# Bachelorarbeit.net
KiCad netlist of a schematic drawn in EAGLE
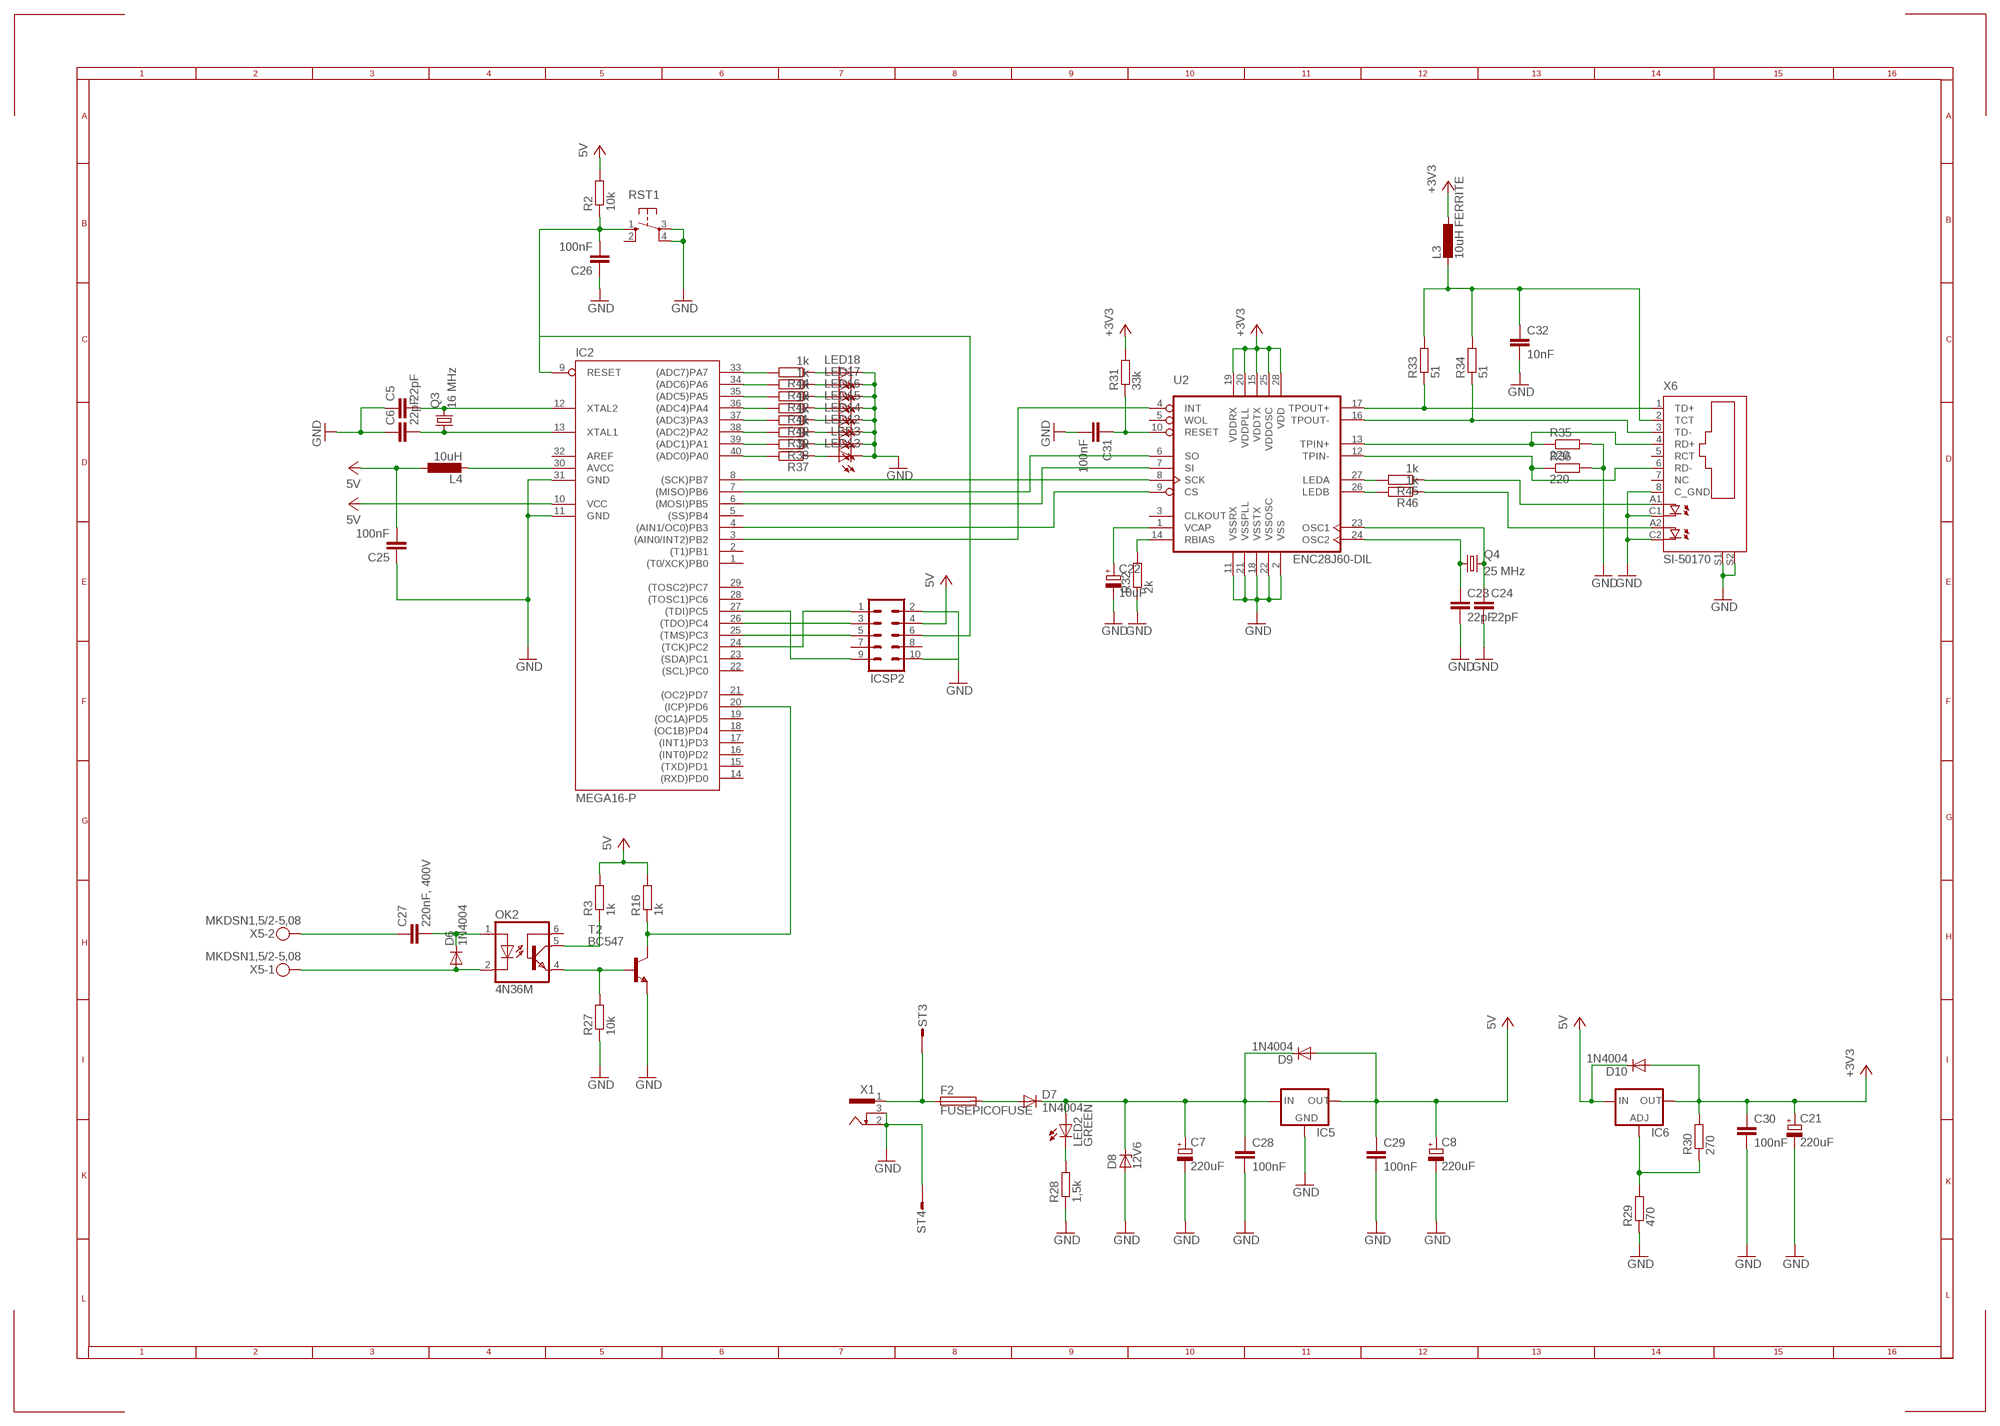
[diagram p0: schematic, sheet 1]

(export (version "E")
  (design (tool "Eeschema 10.0.6"))
  (components
    (comp (ref "C5")
      (value "22pF")
      (footprint "eagle-import:C025-024X044")
      (libsource (lib "eagle-import") (part "C-EU025-024X044"))
    )
    (comp (ref "C6")
      (value "22pF")
      (footprint "eagle-import:C025-024X044")
      (libsource (lib "eagle-import") (part "C-EU025-024X044"))
    )
    (comp (ref "C7")
      (value "220uF")
      (footprint "eagle-import:E3,5-8")
      (libsource (lib "eagle-import") (part "CPOL-EUE3.5-8"))
    )
    (comp (ref "C8")
      (value "220uF")
      (footprint "eagle-import:E3,5-8")
      (libsource (lib "eagle-import") (part "CPOL-EUE3.5-8"))
    )
    (comp (ref "C21")
      (value "220uF")
      (footprint "eagle-import:E3,5-8")
      (libsource (lib "eagle-import") (part "CPOL-EUE3.5-8"))
    )
    (comp (ref "C22")
      (value "10uF")
      (footprint "eagle-import:E3,5-8")
      (libsource (lib "eagle-import") (part "CPOL-EUE3.5-8"))
    )
    (comp (ref "C23")
      (value "22pF")
      (footprint "eagle-import:C025-024X044")
      (libsource (lib "eagle-import") (part "C-EU025-024X044"))
    )
    (comp (ref "C24")
      (value "22pF")
      (footprint "eagle-import:C025-024X044")
      (libsource (lib "eagle-import") (part "C-EU025-024X044"))
    )
    (comp (ref "C25")
      (value "100nF")
      (footprint "eagle-import:C025-025X050")
      (libsource (lib "eagle-import") (part "C-EU025-025X050"))
    )
    (comp (ref "C26")
      (value "100nF")
      (footprint "eagle-import:C025-025X050")
      (libsource (lib "eagle-import") (part "C-EU025-025X050"))
    )
    (comp (ref "C27")
      (value "220nF, 400V")
      (footprint "eagle-import:C025-025X050")
      (libsource (lib "eagle-import") (part "C-EU025-025X050"))
    )
    (comp (ref "C28")
      (value "100nF")
      (footprint "eagle-import:C025-025X050")
      (libsource (lib "eagle-import") (part "C-EU025-025X050"))
    )
    (comp (ref "C29")
      (value "100nF")
      (footprint "eagle-import:C025-025X050")
      (libsource (lib "eagle-import") (part "C-EU025-025X050"))
    )
    (comp (ref "C30")
      (value "100nF")
      (footprint "eagle-import:C025-025X050")
      (libsource (lib "eagle-import") (part "C-EU025-025X050"))
    )
    (comp (ref "C31")
      (value "100nF")
      (footprint "eagle-import:C025-025X050")
      (libsource (lib "eagle-import") (part "C-EU025-025X050"))
    )
    (comp (ref "C32")
      (value "10nF")
      (footprint "eagle-import:C025-025X050")
      (libsource (lib "eagle-import") (part "C-EU025-025X050"))
    )
    (comp (ref "D6")
      (value "1N4004")
      (footprint "eagle-import:DO41-10")
      (libsource (lib "eagle-import") (part "1N4004"))
    )
    (comp (ref "D7")
      (value "1N4004")
      (footprint "eagle-import:DO41-10")
      (libsource (lib "eagle-import") (part "1N4004"))
    )
    (comp (ref "D8")
      (value "12V6")
      (footprint "eagle-import:DO34Z7")
      (libsource (lib "eagle-import") (part "BZX90"))
    )
    (comp (ref "D9")
      (value "1N4004")
      (footprint "eagle-import:DO41-10")
      (libsource (lib "eagle-import") (part "1N4004"))
    )
    (comp (ref "D10")
      (value "1N4004")
      (footprint "eagle-import:DO41-10")
      (libsource (lib "eagle-import") (part "1N4004"))
    )
    (comp (ref "F2")
      (value "FUSEPICOFUSE")
      (footprint "eagle-import:PICOFUSE")
      (libsource (lib "eagle-import") (part "FUSEPICOFUSE"))
    )
    (comp (ref "IC2")
      (value "MEGA16-P")
      (footprint "eagle-import:DIL40")
      (fields (field (name "MPN") "ATMEGA16-16PU"))
      (libsource (lib "eagle-import") (part "MEGA16-P"))
    )
    (comp (ref "IC5")
      (value "78XXS")
      (footprint "eagle-import:78XXS")
      (libsource (lib "eagle-import") (part "78XXS"))
    )
    (comp (ref "IC6")
      (value "LM317TS")
      (footprint "eagle-import:317TS")
      (libsource (lib "eagle-import") (part "LM317TS"))
    )
    (comp (ref "ICSP2")
      (value "10V")
      (footprint "eagle-import:10V")
      (libsource (lib "eagle-import") (part "10V"))
    )
    (comp (ref "L3")
      (value "10uH FERRITE")
      (footprint "eagle-import:0204_5")
      (libsource (lib "eagle-import") (part "L-EU0204/5"))
    )
    (comp (ref "L4")
      (value "10uH")
      (footprint "eagle-import:0204_5")
      (libsource (lib "eagle-import") (part "L-EU0204/5"))
    )
    (comp (ref "LED2")
      (value "GREEN")
      (footprint "eagle-import:LED3MM")
      (libsource (lib "eagle-import") (part "LED3MM"))
    )
    (comp (ref "LED3")
      (value "LED3MM")
      (footprint "eagle-import:LED3MM")
      (libsource (lib "eagle-import") (part "LED3MM"))
    )
    (comp (ref "LED12")
      (value "LED3MM")
      (footprint "eagle-import:LED3MM")
      (libsource (lib "eagle-import") (part "LED3MM"))
    )
    (comp (ref "LED13")
      (value "LED3MM")
      (footprint "eagle-import:LED3MM")
      (libsource (lib "eagle-import") (part "LED3MM"))
    )
    (comp (ref "LED14")
      (value "LED3MM")
      (footprint "eagle-import:LED3MM")
      (libsource (lib "eagle-import") (part "LED3MM"))
    )
    (comp (ref "LED15")
      (value "LED3MM")
      (footprint "eagle-import:LED3MM")
      (libsource (lib "eagle-import") (part "LED3MM"))
    )
    (comp (ref "LED16")
      (value "LED3MM")
      (footprint "eagle-import:LED3MM")
      (libsource (lib "eagle-import") (part "LED3MM"))
    )
    (comp (ref "LED17")
      (value "LED3MM")
      (footprint "eagle-import:LED3MM")
      (libsource (lib "eagle-import") (part "LED3MM"))
    )
    (comp (ref "LED18")
      (value "LED3MM")
      (footprint "eagle-import:LED3MM")
      (libsource (lib "eagle-import") (part "LED3MM"))
    )
    (comp (ref "OK2")
      (value "4N36M")
      (footprint "eagle-import:DIL06")
      (fields (field (name "MPN") "4N36-M"))
      (libsource (lib "eagle-import") (part "4N?M36"))
    )
    (comp (ref "Q3")
      (value "16 MHz")
      (footprint "eagle-import:HC49U-V")
      (libsource (lib "eagle-import") (part "CRYSTALHC49U-V"))
    )
    (comp (ref "Q4")
      (value "25 MHz")
      (footprint "eagle-import:HC49U-V")
      (libsource (lib "eagle-import") (part "CRYSTALHC49U-V"))
    )
    (comp (ref "R2")
      (value "10k")
      (footprint "eagle-import:0207_10")
      (libsource (lib "eagle-import") (part "R-EU_0207/10"))
    )
    (comp (ref "R3")
      (value "1k")
      (footprint "eagle-import:0207_10")
      (libsource (lib "eagle-import") (part "R-EU_0207/10"))
    )
    (comp (ref "R16")
      (value "1k")
      (footprint "eagle-import:0207_10")
      (libsource (lib "eagle-import") (part "R-EU_0207/10"))
    )
    (comp (ref "R27")
      (value "10k")
      (footprint "eagle-import:0207_10")
      (libsource (lib "eagle-import") (part "R-EU_0207/10"))
    )
    (comp (ref "R28")
      (value "1,5k")
      (footprint "eagle-import:0207_10")
      (libsource (lib "eagle-import") (part "R-EU_0207/10"))
    )
    (comp (ref "R29")
      (value "470")
      (footprint "eagle-import:0207_10")
      (libsource (lib "eagle-import") (part "R-EU_0207/10"))
    )
    (comp (ref "R30")
      (value "270")
      (footprint "eagle-import:0207_10")
      (libsource (lib "eagle-import") (part "R-EU_0207/10"))
    )
    (comp (ref "R31")
      (value "33k")
      (footprint "eagle-import:0207_10")
      (libsource (lib "eagle-import") (part "R-EU_0207/10"))
    )
    (comp (ref "R32")
      (value "2k")
      (footprint "eagle-import:0207_10")
      (libsource (lib "eagle-import") (part "R-EU_0207/10"))
    )
    (comp (ref "R33")
      (value "51")
      (footprint "eagle-import:0207_10")
      (libsource (lib "eagle-import") (part "R-EU_0207/10"))
    )
    (comp (ref "R34")
      (value "51")
      (footprint "eagle-import:0207_10")
      (libsource (lib "eagle-import") (part "R-EU_0207/10"))
    )
    (comp (ref "R35")
      (value "220")
      (footprint "eagle-import:0207_10")
      (libsource (lib "eagle-import") (part "R-EU_0207/10"))
    )
    (comp (ref "R36")
      (value "220")
      (footprint "eagle-import:0207_10")
      (libsource (lib "eagle-import") (part "R-EU_0207/10"))
    )
    (comp (ref "R37")
      (value "1k")
      (footprint "eagle-import:0207_10")
      (libsource (lib "eagle-import") (part "R-EU_0207/10"))
    )
    (comp (ref "R38")
      (value "1k")
      (footprint "eagle-import:0207_10")
      (libsource (lib "eagle-import") (part "R-EU_0207/10"))
    )
    (comp (ref "R39")
      (value "1k")
      (footprint "eagle-import:0207_10")
      (libsource (lib "eagle-import") (part "R-EU_0207/10"))
    )
    (comp (ref "R40")
      (value "1k")
      (footprint "eagle-import:0207_10")
      (libsource (lib "eagle-import") (part "R-EU_0207/10"))
    )
    (comp (ref "R41")
      (value "1k")
      (footprint "eagle-import:0207_10")
      (libsource (lib "eagle-import") (part "R-EU_0207/10"))
    )
    (comp (ref "R42")
      (value "1k")
      (footprint "eagle-import:0207_10")
      (libsource (lib "eagle-import") (part "R-EU_0207/10"))
    )
    (comp (ref "R43")
      (value "1k")
      (footprint "eagle-import:0207_10")
      (libsource (lib "eagle-import") (part "R-EU_0207/10"))
    )
    (comp (ref "R44")
      (value "1k")
      (footprint "eagle-import:0207_10")
      (libsource (lib "eagle-import") (part "R-EU_0207/10"))
    )
    (comp (ref "R45")
      (value "1k")
      (footprint "eagle-import:0207_10")
      (libsource (lib "eagle-import") (part "R-EU_0207/10"))
    )
    (comp (ref "R46")
      (value "1k")
      (footprint "eagle-import:0207_10")
      (libsource (lib "eagle-import") (part "R-EU_0207/10"))
    )
    (comp (ref "RST1")
      (value "10-XX")
      (footprint "eagle-import:B3F-10XX")
      (fields (field (name "MPN") "B3F-1000"))
      (libsource (lib "eagle-import") (part "10-XX"))
    )
    (comp (ref "ST3")
      (value "ST2,8")
      (footprint "eagle-import:ST2,8")
      (libsource (lib "eagle-import") (part "ST2,8"))
    )
    (comp (ref "ST4")
      (value "ST2,8")
      (footprint "eagle-import:ST2,8")
      (libsource (lib "eagle-import") (part "ST2,8"))
    )
    (comp (ref "T2")
      (value "BC547")
      (footprint "eagle-import:TO92")
      (libsource (lib "eagle-import") (part "BC547"))
    )
    (comp (ref "U2")
      (value "ENC28J60-DIL")
      (footprint "eagle-import:DIL28-3")
      (libsource (lib "eagle-import") (part "ENC28J60-DIL"))
    )
    (comp (ref "X1")
      (value "SCD-014A")
      (footprint "eagle-import:SCD-014-A")
      (libsource (lib "eagle-import") (part "SCD-014A"))
    )
    (comp (ref "X5")
      (value "MKDSN1,5/2-5,08")
      (footprint "eagle-import:MKDSN1,5_2-5,08")
      (fields (field (name "MPN") "MKDSN 1,5/2-5.08"))
      (libsource (lib "eagle-import") (part "MKDSN1,5/2-5,08"))
    )
    (comp (ref "X6")
      (value "SI-50170")
      (footprint "eagle-import:SI-50170")
      (libsource (lib "eagle-import") (part "SI-50170"))
    )
  )
  (nets
    (net (code "1") (name "+3V3") (class "Default")
      (node (ref "C21") (pin "+") (pinfunction "+_+") (pintype "passive"))
      (node (ref "C25") (pin "2") (pinfunction "2_2") (pintype "passive"))
      (node (ref "C29") (pin "1") (pinfunction "1_1") (pintype "passive"))
      (node (ref "C30") (pin "1") (pinfunction "1_1") (pintype "passive"))
      (node (ref "C8") (pin "+") (pinfunction "+_+") (pintype "passive"))
      (node (ref "D10") (pin "A") (pinfunction "A_A") (pintype "passive"))
      (node (ref "D10") (pin "C") (pinfunction "C_C") (pintype "passive"))
      (node (ref "D9") (pin "A") (pinfunction "A_A") (pintype "passive"))
      (node (ref "IC2") (pin "10") (pinfunction "VCC_10") (pintype "power_in"))
      (node (ref "IC5") (pin "OUT") (pinfunction "OUT_OUT") (pintype "passive"))
      (node (ref "IC6") (pin "2") (pinfunction "OUT_2") (pintype "passive"))
      (node (ref "IC6") (pin "3") (pinfunction "IN_3") (pintype "input"))
      (node (ref "ICSP2") (pin "4") (pinfunction "4_4") (pintype "passive"))
      (node (ref "L3") (pin "1") (pinfunction "1_1") (pintype "passive"))
      (node (ref "L4") (pin "1") (pinfunction "1_1") (pintype "passive"))
      (node (ref "R16") (pin "2") (pinfunction "2_2") (pintype "passive"))
      (node (ref "R2") (pin "2") (pinfunction "2_2") (pintype "passive"))
      (node (ref "R3") (pin "2") (pinfunction "2_2") (pintype "passive"))
      (node (ref "R30") (pin "2") (pinfunction "2_2") (pintype "passive"))
      (node (ref "R31") (pin "2") (pinfunction "2_2") (pintype "passive"))
      (node (ref "U2") (pin "15") (pinfunction "VDDTX_15") (pintype "power_in"))
      (node (ref "U2") (pin "19") (pinfunction "VDDRX_19") (pintype "power_in"))
      (node (ref "U2") (pin "20") (pinfunction "VDDPLL_20") (pintype "power_in"))
      (node (ref "U2") (pin "25") (pinfunction "VDDOSC_25") (pintype "power_in"))
      (node (ref "U2") (pin "28") (pinfunction "VDD_28") (pintype "power_in"))
    )
    (net (code "2") (name "GND") (class "Default")
      (node (ref "C21") (pin "-") (pinfunction "-_-") (pintype "passive"))
      (node (ref "C22") (pin "-") (pinfunction "-_-") (pintype "passive"))
      (node (ref "C23") (pin "2") (pinfunction "2_2") (pintype "passive"))
      (node (ref "C24") (pin "2") (pinfunction "2_2") (pintype "passive"))
      (node (ref "C25") (pin "1") (pinfunction "1_1") (pintype "passive"))
      (node (ref "C26") (pin "1") (pinfunction "1_1") (pintype "passive"))
      (node (ref "C28") (pin "2") (pinfunction "2_2") (pintype "passive"))
      (node (ref "C29") (pin "2") (pinfunction "2_2") (pintype "passive"))
      (node (ref "C30") (pin "2") (pinfunction "2_2") (pintype "passive"))
      (node (ref "C31") (pin "2") (pinfunction "2_2") (pintype "passive"))
      (node (ref "C32") (pin "2") (pinfunction "2_2") (pintype "passive"))
      (node (ref "C5") (pin "1") (pinfunction "1_1") (pintype "passive"))
      (node (ref "C6") (pin "1") (pinfunction "1_1") (pintype "passive"))
      (node (ref "C7") (pin "-") (pinfunction "-_-") (pintype "passive"))
      (node (ref "C8") (pin "-") (pinfunction "-_-") (pintype "passive"))
      (node (ref "D8") (pin "A") (pinfunction "A_A") (pintype "passive"))
      (node (ref "IC2") (pin "11") (pinfunction "GND_11") (pintype "power_in"))
      (node (ref "IC2") (pin "31") (pinfunction "GND_31") (pintype "power_in"))
      (node (ref "IC5") (pin "GND") (pinfunction "GND_GND") (pintype "input"))
      (node (ref "ICSP2") (pin "10") (pinfunction "10_10") (pintype "passive"))
      (node (ref "ICSP2") (pin "2") (pinfunction "2_2") (pintype "passive"))
      (node (ref "LED12") (pin "K") (pinfunction "C_K") (pintype "passive"))
      (node (ref "LED13") (pin "K") (pinfunction "C_K") (pintype "passive"))
      (node (ref "LED14") (pin "K") (pinfunction "C_K") (pintype "passive"))
      (node (ref "LED15") (pin "K") (pinfunction "C_K") (pintype "passive"))
      (node (ref "LED16") (pin "K") (pinfunction "C_K") (pintype "passive"))
      (node (ref "LED17") (pin "K") (pinfunction "C_K") (pintype "passive"))
      (node (ref "LED18") (pin "K") (pinfunction "C_K") (pintype "passive"))
      (node (ref "LED3") (pin "K") (pinfunction "C_K") (pintype "passive"))
      (node (ref "R27") (pin "1") (pinfunction "1_1") (pintype "passive"))
      (node (ref "R28") (pin "1") (pinfunction "1_1") (pintype "passive"))
      (node (ref "R29") (pin "1") (pinfunction "1_1") (pintype "passive"))
      (node (ref "R32") (pin "1") (pinfunction "1_1") (pintype "passive"))
      (node (ref "R35") (pin "2") (pinfunction "2_2") (pintype "passive"))
      (node (ref "R36") (pin "2") (pinfunction "2_2") (pintype "passive"))
      (node (ref "RST1") (pin "3") (pinfunction "P_3") (pintype "passive"))
      (node (ref "RST1") (pin "4") (pinfunction "P1_4") (pintype "passive"))
      (node (ref "ST4") (pin "1") (pinfunction "ST_1") (pintype "passive"))
      (node (ref "T2") (pin "1") (pinfunction "E_1") (pintype "passive"))
      (node (ref "U2") (pin "11") (pinfunction "VSSRX_11") (pintype "power_in"))
      (node (ref "U2") (pin "18") (pinfunction "VSSTX_18") (pintype "power_in"))
      (node (ref "U2") (pin "2") (pinfunction "VSS_2") (pintype "power_in"))
      (node (ref "U2") (pin "21") (pinfunction "VSSPLL_21") (pintype "power_in"))
      (node (ref "U2") (pin "22") (pinfunction "VSSOSC_22") (pintype "power_in"))
      (node (ref "X1") (pin "2") (pinfunction "2_2") (pintype "passive"))
      (node (ref "X1") (pin "3") (pinfunction "3_3") (pintype "passive"))
      (node (ref "X6") (pin "8") (pinfunction "C_GND_8") (pintype "passive"))
      (node (ref "X6") (pin "C1") (pinfunction "C_C1") (pintype "passive"))
      (node (ref "X6") (pin "C2") (pinfunction "C1_C2") (pintype "passive"))
      (node (ref "X6") (pin "S1") (pinfunction "S1_S1") (pintype "passive"))
      (node (ref "X6") (pin "S2") (pinfunction "S2_S2") (pintype "passive"))
    )
    (net (code "3") (name "Net-(C28-Pad1)") (class "Default")
      (node (ref "C28") (pin "1") (pinfunction "1_1") (pintype "passive"))
      (node (ref "C7") (pin "+") (pinfunction "+_+") (pintype "passive"))
      (node (ref "D7") (pin "C") (pinfunction "C_C") (pintype "passive"))
      (node (ref "D8") (pin "C") (pinfunction "C_C") (pintype "passive"))
      (node (ref "D9") (pin "C") (pinfunction "C_C") (pintype "passive"))
      (node (ref "IC5") (pin "IN") (pinfunction "IN_IN") (pintype "input"))
      (node (ref "LED2") (pin "A") (pinfunction "A_A") (pintype "passive"))
    )
    (net (code "4") (name "Net-(D7-PadA)") (class "Default")
      (node (ref "D7") (pin "A") (pinfunction "A_A") (pintype "passive"))
      (node (ref "F2") (pin "2") (pinfunction "2_2") (pintype "passive"))
    )
    (net (code "5") (name "Net-(IC2-(ADC0)PA0)") (class "Default")
      (node (ref "IC2") (pin "40") (pinfunction "(ADC0)PA0_40") (pintype "bidirectional"))
      (node (ref "R37") (pin "2") (pinfunction "2_2") (pintype "passive"))
    )
    (net (code "6") (name "Net-(IC2-(ADC1)PA1)") (class "Default")
      (node (ref "IC2") (pin "39") (pinfunction "(ADC1)PA1_39") (pintype "bidirectional"))
      (node (ref "R38") (pin "2") (pinfunction "2_2") (pintype "passive"))
    )
    (net (code "7") (name "Net-(IC2-(ADC2)PA2)") (class "Default")
      (node (ref "IC2") (pin "38") (pinfunction "(ADC2)PA2_38") (pintype "bidirectional"))
      (node (ref "R39") (pin "2") (pinfunction "2_2") (pintype "passive"))
    )
    (net (code "8") (name "Net-(IC2-(ADC3)PA3)") (class "Default")
      (node (ref "IC2") (pin "37") (pinfunction "(ADC3)PA3_37") (pintype "bidirectional"))
      (node (ref "R40") (pin "2") (pinfunction "2_2") (pintype "passive"))
    )
    (net (code "9") (name "Net-(IC2-(ADC4)PA4)") (class "Default")
      (node (ref "IC2") (pin "36") (pinfunction "(ADC4)PA4_36") (pintype "bidirectional"))
      (node (ref "R41") (pin "2") (pinfunction "2_2") (pintype "passive"))
    )
    (net (code "10") (name "Net-(IC2-(ADC5)PA5)") (class "Default")
      (node (ref "IC2") (pin "35") (pinfunction "(ADC5)PA5_35") (pintype "bidirectional"))
      (node (ref "R42") (pin "2") (pinfunction "2_2") (pintype "passive"))
    )
    (net (code "11") (name "Net-(IC2-(ADC6)PA6)") (class "Default")
      (node (ref "IC2") (pin "34") (pinfunction "(ADC6)PA6_34") (pintype "bidirectional"))
      (node (ref "R43") (pin "2") (pinfunction "2_2") (pintype "passive"))
    )
    (net (code "12") (name "Net-(IC2-(ADC7)PA7)") (class "Default")
      (node (ref "IC2") (pin "33") (pinfunction "(ADC7)PA7_33") (pintype "bidirectional"))
      (node (ref "R44") (pin "2") (pinfunction "2_2") (pintype "passive"))
    )
    (net (code "13") (name "Net-(IC2-(AIN0{slash}INT2)PB2)") (class "Default")
      (node (ref "IC2") (pin "3") (pinfunction "(AIN0/INT2)PB2_3") (pintype "bidirectional"))
      (node (ref "U2") (pin "4") (pinfunction "INT_4") (pintype "output"))
    )
    (net (code "14") (name "Net-(IC2-(AIN1{slash}OC0)PB3)") (class "Default")
      (node (ref "IC2") (pin "4") (pinfunction "(AIN1/OC0)PB3_4") (pintype "bidirectional"))
      (node (ref "U2") (pin "9") (pinfunction "CS_9") (pintype "input"))
    )
    (net (code "15") (name "Net-(IC2-(ICP)PD6)") (class "Default")
      (node (ref "IC2") (pin "20") (pinfunction "(ICP)PD6_20") (pintype "bidirectional"))
      (node (ref "R16") (pin "1") (pinfunction "1_1") (pintype "passive"))
      (node (ref "T2") (pin "3") (pinfunction "C_3") (pintype "passive"))
    )
    (net (code "16") (name "Net-(IC2-(MISO)PB6)") (class "Default")
      (node (ref "IC2") (pin "7") (pinfunction "(MISO)PB6_7") (pintype "bidirectional"))
      (node (ref "U2") (pin "6") (pinfunction "SO_6") (pintype "open_collector"))
    )
    (net (code "17") (name "Net-(IC2-(MOSI)PB5)") (class "Default")
      (node (ref "IC2") (pin "6") (pinfunction "(MOSI)PB5_6") (pintype "bidirectional"))
      (node (ref "U2") (pin "7") (pinfunction "SI_7") (pintype "input"))
    )
    (net (code "18") (name "Net-(IC2-(SCK)PB7)") (class "Default")
      (node (ref "IC2") (pin "8") (pinfunction "(SCK)PB7_8") (pintype "bidirectional"))
      (node (ref "U2") (pin "8") (pinfunction "SCK_8") (pintype "input"))
    )
    (net (code "19") (name "Net-(IC2-(TCK)PC2)") (class "Default")
      (node (ref "IC2") (pin "24") (pinfunction "(TCK)PC2_24") (pintype "bidirectional"))
      (node (ref "ICSP2") (pin "1") (pinfunction "1_1") (pintype "passive"))
    )
    (net (code "20") (name "Net-(IC2-(TDI)PC5)") (class "Default")
      (node (ref "IC2") (pin "27") (pinfunction "(TDI)PC5_27") (pintype "bidirectional"))
      (node (ref "ICSP2") (pin "9") (pinfunction "9_9") (pintype "passive"))
    )
    (net (code "21") (name "Net-(IC2-(TDO)PC4)") (class "Default")
      (node (ref "IC2") (pin "26") (pinfunction "(TDO)PC4_26") (pintype "bidirectional"))
      (node (ref "ICSP2") (pin "3") (pinfunction "3_3") (pintype "passive"))
    )
    (net (code "22") (name "Net-(IC2-(TMS)PC3)") (class "Default")
      (node (ref "IC2") (pin "25") (pinfunction "(TMS)PC3_25") (pintype "bidirectional"))
      (node (ref "ICSP2") (pin "5") (pinfunction "5_5") (pintype "passive"))
    )
    (net (code "23") (name "Net-(IC2-AVCC)") (class "Default")
      (node (ref "IC2") (pin "30") (pinfunction "AVCC_30") (pintype "power_in"))
      (node (ref "L4") (pin "2") (pinfunction "2_2") (pintype "passive"))
    )
    (net (code "24") (name "Net-(IC2-RESET)") (class "Default")
      (node (ref "C26") (pin "2") (pinfunction "2_2") (pintype "passive"))
      (node (ref "IC2") (pin "9") (pinfunction "RESET_9") (pintype "input"))
      (node (ref "ICSP2") (pin "6") (pinfunction "6_6") (pintype "passive"))
      (node (ref "R2") (pin "1") (pinfunction "1_1") (pintype "passive"))
      (node (ref "RST1") (pin "1") (pinfunction "S_1") (pintype "passive"))
    )
    (net (code "25") (name "Net-(IC2-XTAL1)") (class "Default")
      (node (ref "C6") (pin "2") (pinfunction "2_2") (pintype "passive"))
      (node (ref "IC2") (pin "13") (pinfunction "XTAL1_13") (pintype "bidirectional"))
      (node (ref "Q3") (pin "1") (pinfunction "1_1") (pintype "passive"))
    )
    (net (code "26") (name "Net-(IC2-XTAL2)") (class "Default")
      (node (ref "C5") (pin "2") (pinfunction "2_2") (pintype "passive"))
      (node (ref "IC2") (pin "12") (pinfunction "XTAL2_12") (pintype "bidirectional"))
      (node (ref "Q3") (pin "2") (pinfunction "2_2") (pintype "passive"))
    )
    (net (code "27") (name "Net-(IC6-ADJ)") (class "Default")
      (node (ref "IC6") (pin "1") (pinfunction "ADJ_1") (pintype "input"))
      (node (ref "R29") (pin "2") (pinfunction "2_2") (pintype "passive"))
      (node (ref "R30") (pin "1") (pinfunction "1_1") (pintype "passive"))
    )
    (net (code "28") (name "Net-(LED2-C)") (class "Default")
      (node (ref "LED2") (pin "K") (pinfunction "C_K") (pintype "passive"))
      (node (ref "R28") (pin "2") (pinfunction "2_2") (pintype "passive"))
    )
    (net (code "29") (name "Net-(LED3-PadA)") (class "Default")
      (node (ref "LED3") (pin "A") (pinfunction "A_A") (pintype "passive"))
      (node (ref "R38") (pin "1") (pinfunction "1_1") (pintype "passive"))
    )
    (net (code "30") (name "Net-(LED12-PadA)") (class "Default")
      (node (ref "LED12") (pin "A") (pinfunction "A_A") (pintype "passive"))
      (node (ref "R39") (pin "1") (pinfunction "1_1") (pintype "passive"))
    )
    (net (code "31") (name "Net-(LED13-PadA)") (class "Default")
      (node (ref "LED13") (pin "A") (pinfunction "A_A") (pintype "passive"))
      (node (ref "R37") (pin "1") (pinfunction "1_1") (pintype "passive"))
    )
    (net (code "32") (name "Net-(LED14-PadA)") (class "Default")
      (node (ref "LED14") (pin "A") (pinfunction "A_A") (pintype "passive"))
      (node (ref "R40") (pin "1") (pinfunction "1_1") (pintype "passive"))
    )
    (net (code "33") (name "Net-(LED15-PadA)") (class "Default")
      (node (ref "LED15") (pin "A") (pinfunction "A_A") (pintype "passive"))
      (node (ref "R41") (pin "1") (pinfunction "1_1") (pintype "passive"))
    )
    (net (code "34") (name "Net-(LED16-PadA)") (class "Default")
      (node (ref "LED16") (pin "A") (pinfunction "A_A") (pintype "passive"))
      (node (ref "R42") (pin "1") (pinfunction "1_1") (pintype "passive"))
    )
    (net (code "35") (name "Net-(LED17-PadA)") (class "Default")
      (node (ref "LED17") (pin "A") (pinfunction "A_A") (pintype "passive"))
      (node (ref "R43") (pin "1") (pinfunction "1_1") (pintype "passive"))
    )
    (net (code "36") (name "Net-(LED18-PadA)") (class "Default")
      (node (ref "LED18") (pin "A") (pinfunction "A_A") (pintype "passive"))
      (node (ref "R44") (pin "1") (pinfunction "1_1") (pintype "passive"))
    )
    (net (code "37") (name "Net-(OK2-A)") (class "Default")
      (node (ref "C27") (pin "2") (pinfunction "2_2") (pintype "passive"))
      (node (ref "D6") (pin "C") (pinfunction "C_C") (pintype "passive"))
      (node (ref "OK2") (pin "1") (pinfunction "A_1") (pintype "passive"))
    )
    (net (code "38") (name "Net-(OK2-C)") (class "Default")
      (node (ref "D6") (pin "A") (pinfunction "A_A") (pintype "passive"))
      (node (ref "OK2") (pin "2") (pinfunction "C_2") (pintype "passive"))
      (node (ref "X5") (pin "1") (pinfunction "KL_1") (pintype "passive"))
    )
    (net (code "39") (name "Net-(OK2-COL)") (class "Default")
      (node (ref "OK2") (pin "5") (pinfunction "COL_5") (pintype "passive"))
      (node (ref "R3") (pin "1") (pinfunction "1_1") (pintype "passive"))
    )
    (net (code "40") (name "Net-(OK2-EMI)") (class "Default")
      (node (ref "OK2") (pin "4") (pinfunction "EMI_4") (pintype "passive"))
      (node (ref "R27") (pin "2") (pinfunction "2_2") (pintype "passive"))
      (node (ref "T2") (pin "2") (pinfunction "B_2") (pintype "passive"))
    )
    (net (code "41") (name "Net-(ST3-ST)") (class "Default")
      (node (ref "F2") (pin "1") (pinfunction "1_1") (pintype "passive"))
      (node (ref "ST3") (pin "1") (pinfunction "ST_1") (pintype "passive"))
      (node (ref "X1") (pin "1") (pinfunction "1_1") (pintype "passive"))
    )
    (net (code "42") (name "Net-(U2-LEDA)") (class "Default")
      (node (ref "R45") (pin "2") (pinfunction "2_2") (pintype "passive"))
      (node (ref "U2") (pin "27") (pinfunction "LEDA_27") (pintype "output"))
    )
    (net (code "43") (name "Net-(U2-LEDB)") (class "Default")
      (node (ref "R46") (pin "2") (pinfunction "2_2") (pintype "passive"))
      (node (ref "U2") (pin "26") (pinfunction "LEDB_26") (pintype "output"))
    )
    (net (code "44") (name "Net-(U2-OSC1)") (class "Default")
      (node (ref "C24") (pin "1") (pinfunction "1_1") (pintype "passive"))
      (node (ref "Q4") (pin "2") (pinfunction "2_2") (pintype "passive"))
      (node (ref "U2") (pin "23") (pinfunction "OSC1_23") (pintype "input"))
    )
    (net (code "45") (name "Net-(U2-OSC2)") (class "Default")
      (node (ref "C23") (pin "1") (pinfunction "1_1") (pintype "passive"))
      (node (ref "Q4") (pin "1") (pinfunction "1_1") (pintype "passive"))
      (node (ref "U2") (pin "24") (pinfunction "OSC2_24") (pintype "output"))
    )
    (net (code "46") (name "Net-(U2-RBIAS)") (class "Default")
      (node (ref "R32") (pin "2") (pinfunction "2_2") (pintype "passive"))
      (node (ref "U2") (pin "14") (pinfunction "RBIAS_14") (pintype "passive"))
    )
    (net (code "47") (name "Net-(U2-RESET)") (class "Default")
      (node (ref "C31") (pin "1") (pinfunction "1_1") (pintype "passive"))
      (node (ref "R31") (pin "1") (pinfunction "1_1") (pintype "passive"))
      (node (ref "U2") (pin "10") (pinfunction "RESET_10") (pintype "input"))
    )
    (net (code "48") (name "Net-(U2-TPIN+)") (class "Default")
      (node (ref "R35") (pin "1") (pinfunction "1_1") (pintype "passive"))
      (node (ref "U2") (pin "13") (pinfunction "TPIN+_13") (pintype "input"))
      (node (ref "X6") (pin "4") (pinfunction "RD+_4") (pintype "passive"))
    )
    (net (code "49") (name "Net-(U2-TPIN-)") (class "Default")
      (node (ref "R36") (pin "1") (pinfunction "1_1") (pintype "passive"))
      (node (ref "U2") (pin "12") (pinfunction "TPIN-_12") (pintype "input"))
      (node (ref "X6") (pin "6") (pinfunction "RD-_6") (pintype "passive"))
    )
    (net (code "50") (name "Net-(U2-TPOUT+)") (class "Default")
      (node (ref "R33") (pin "1") (pinfunction "1_1") (pintype "passive"))
      (node (ref "U2") (pin "17") (pinfunction "TPOUT+_17") (pintype "output"))
      (node (ref "X6") (pin "1") (pinfunction "TD+_1") (pintype "passive"))
    )
    (net (code "51") (name "Net-(U2-TPOUT-)") (class "Default")
      (node (ref "R34") (pin "1") (pinfunction "1_1") (pintype "passive"))
      (node (ref "U2") (pin "16") (pinfunction "TPOUT-_16") (pintype "output"))
      (node (ref "X6") (pin "3") (pinfunction "TD-_3") (pintype "passive"))
    )
    (net (code "52") (name "Net-(U2-VCAP)") (class "Default")
      (node (ref "C22") (pin "+") (pinfunction "+_+") (pintype "passive"))
      (node (ref "U2") (pin "1") (pinfunction "VCAP_1") (pintype "power_in"))
    )
    (net (code "53") (name "Net-(X5B-KL)") (class "Default")
      (node (ref "C27") (pin "1") (pinfunction "1_1") (pintype "passive"))
      (node (ref "X5") (pin "2") (pinfunction "KL_2") (pintype "passive"))
    )
    (net (code "54") (name "Net-(X6-A)") (class "Default")
      (node (ref "R45") (pin "1") (pinfunction "1_1") (pintype "passive"))
      (node (ref "X6") (pin "A1") (pinfunction "A_A1") (pintype "passive"))
    )
    (net (code "55") (name "Net-(X6-A1)") (class "Default")
      (node (ref "R46") (pin "1") (pinfunction "1_1") (pintype "passive"))
      (node (ref "X6") (pin "A2") (pinfunction "A1_A2") (pintype "passive"))
    )
    (net (code "56") (name "Net-(X6-TCT)") (class "Default")
      (node (ref "C32") (pin "1") (pinfunction "1_1") (pintype "passive"))
      (node (ref "L3") (pin "2") (pinfunction "2_2") (pintype "passive"))
      (node (ref "R33") (pin "2") (pinfunction "2_2") (pintype "passive"))
      (node (ref "R34") (pin "2") (pinfunction "2_2") (pintype "passive"))
      (node (ref "X6") (pin "2") (pinfunction "TCT_2") (pintype "passive"))
    )
    (net (code "57") (name "unconnected-(IC2-(INT0)PD2-Pad16)") (class "Default")
      (node (ref "IC2") (pin "16") (pinfunction "(INT0)PD2_16") (pintype "bidirectional"))
    )
    (net (code "58") (name "unconnected-(IC2-(INT1)PD3-Pad17)") (class "Default")
      (node (ref "IC2") (pin "17") (pinfunction "(INT1)PD3_17") (pintype "bidirectional"))
    )
    (net (code "59") (name "unconnected-(IC2-(OC1A)PD5-Pad19)") (class "Default")
      (node (ref "IC2") (pin "19") (pinfunction "(OC1A)PD5_19") (pintype "bidirectional"))
    )
    (net (code "60") (name "unconnected-(IC2-(OC1B)PD4-Pad18)") (class "Default")
      (node (ref "IC2") (pin "18") (pinfunction "(OC1B)PD4_18") (pintype "bidirectional"))
    )
    (net (code "61") (name "unconnected-(IC2-(OC2)PD7-Pad21)") (class "Default")
      (node (ref "IC2") (pin "21") (pinfunction "(OC2)PD7_21") (pintype "bidirectional"))
    )
    (net (code "62") (name "unconnected-(IC2-(RXD)PD0-Pad14)") (class "Default")
      (node (ref "IC2") (pin "14") (pinfunction "(RXD)PD0_14") (pintype "bidirectional"))
    )
    (net (code "63") (name "unconnected-(IC2-(SCL)PC0-Pad22)") (class "Default")
      (node (ref "IC2") (pin "22") (pinfunction "(SCL)PC0_22") (pintype "bidirectional"))
    )
    (net (code "64") (name "unconnected-(IC2-(SDA)PC1-Pad23)") (class "Default")
      (node (ref "IC2") (pin "23") (pinfunction "(SDA)PC1_23") (pintype "bidirectional"))
    )
    (net (code "65") (name "unconnected-(IC2-(SS)PB4-Pad5)") (class "Default")
      (node (ref "IC2") (pin "5") (pinfunction "(SS)PB4_5") (pintype "bidirectional"))
    )
    (net (code "66") (name "unconnected-(IC2-(T0{slash}XCK)PB0-Pad1)") (class "Default")
      (node (ref "IC2") (pin "1") (pinfunction "(T0/XCK)PB0_1") (pintype "bidirectional"))
    )
    (net (code "67") (name "unconnected-(IC2-(T1)PB1-Pad2)") (class "Default")
      (node (ref "IC2") (pin "2") (pinfunction "(T1)PB1_2") (pintype "bidirectional"))
    )
    (net (code "68") (name "unconnected-(IC2-(TOSC1)PC6-Pad28)") (class "Default")
      (node (ref "IC2") (pin "28") (pinfunction "(TOSC1)PC6_28") (pintype "bidirectional"))
    )
    (net (code "69") (name "unconnected-(IC2-(TOSC2)PC7-Pad29)") (class "Default")
      (node (ref "IC2") (pin "29") (pinfunction "(TOSC2)PC7_29") (pintype "bidirectional"))
    )
    (net (code "70") (name "unconnected-(IC2-(TXD)PD1-Pad15)") (class "Default")
      (node (ref "IC2") (pin "15") (pinfunction "(TXD)PD1_15") (pintype "bidirectional"))
    )
    (net (code "71") (name "unconnected-(IC2-AREF-Pad32)") (class "Default")
      (node (ref "IC2") (pin "32") (pinfunction "AREF_32") (pintype "passive"))
    )
    (net (code "72") (name "unconnected-(ICSP2-Pad7)") (class "Default")
      (node (ref "ICSP2") (pin "7") (pinfunction "7_7") (pintype "passive"))
    )
    (net (code "73") (name "unconnected-(ICSP2-Pad8)") (class "Default")
      (node (ref "ICSP2") (pin "8") (pinfunction "8_8") (pintype "passive"))
    )
    (net (code "74") (name "unconnected-(OK2-BAS-Pad6)") (class "Default")
      (node (ref "OK2") (pin "6") (pinfunction "BAS_6") (pintype "passive"))
    )
    (net (code "75") (name "unconnected-(RST1-S1-Pad2)") (class "Default")
      (node (ref "RST1") (pin "2") (pinfunction "S1_2") (pintype "passive"))
    )
    (net (code "76") (name "unconnected-(U2-CLKOUT-Pad3)") (class "Default")
      (node (ref "U2") (pin "3") (pinfunction "CLKOUT_3") (pintype "output"))
    )
    (net (code "77") (name "unconnected-(U2-WOL-Pad5)") (class "Default")
      (node (ref "U2") (pin "5") (pinfunction "WOL_5") (pintype "output"))
    )
    (net (code "78") (name "unconnected-(X6-NC-Pad7)") (class "Default")
      (node (ref "X6") (pin "7") (pinfunction "NC_7") (pintype "passive"))
    )
    (net (code "79") (name "unconnected-(X6-RCT-Pad5)") (class "Default")
      (node (ref "X6") (pin "5") (pinfunction "RCT_5") (pintype "passive"))
    )
  )
)
